# main.net
KiCad netlist of a schematic drawn in EAGLE
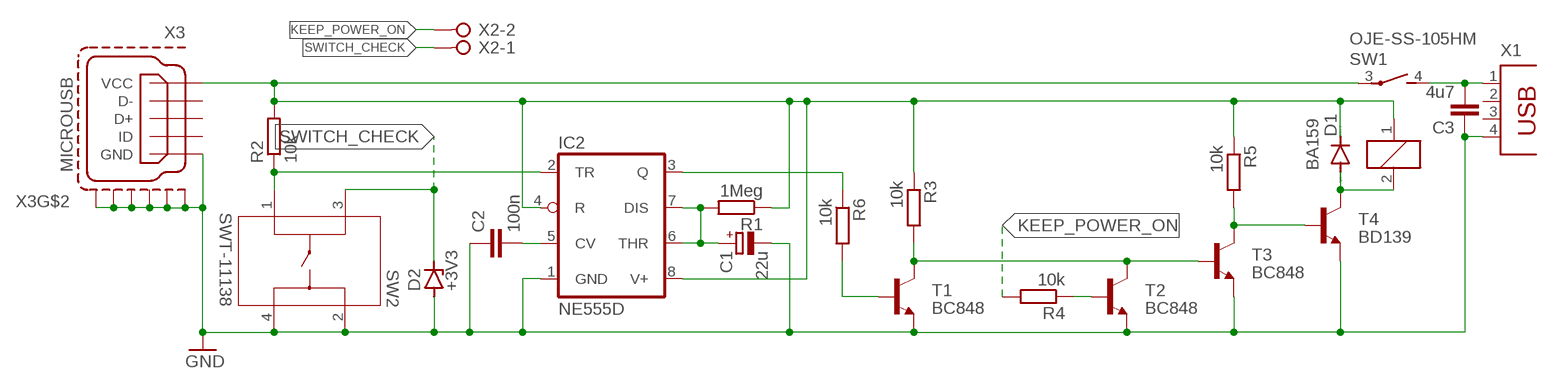
[diagram p0: schematic, sheet 1]

(export (version "E")
  (design (tool "Eeschema 10.0.6"))
  (components
    (comp (ref "C1")
      (value "22u")
      (footprint "eagle-import:SMC_B")
      (libsource (lib "eagle-import") (part "CPOL-EUSMCB"))
    )
    (comp (ref "C2")
      (value "100n")
      (footprint "eagle-import:C0805")
      (libsource (lib "eagle-import") (part "C-EUC0805"))
    )
    (comp (ref "C3")
      (value "4u7")
      (footprint "eagle-import:C050-075X075")
      (libsource (lib "eagle-import") (part "C-EU050-075X075"))
    )
    (comp (ref "D1")
      (value "BA159")
      (footprint "eagle-import:DO41-10")
      (libsource (lib "eagle-import") (part "1N4004"))
    )
    (comp (ref "D2")
      (value "+3V3")
      (footprint "eagle-import:SOD80C")
      (libsource (lib "eagle-import") (part "ZENER-DIODESOD80C"))
    )
    (comp (ref "IC2")
      (value "NE555D")
      (footprint "eagle-import:SO08")
      (libsource (lib "eagle-import") (part "555DNE"))
    )
    (comp (ref "R1")
      (value "1Meg")
      (footprint "eagle-import:R1206")
      (libsource (lib "eagle-import") (part "R-EU_R1206"))
    )
    (comp (ref "R2")
      (value "10k")
      (footprint "eagle-import:R1206")
      (libsource (lib "eagle-import") (part "R-EU_R1206"))
    )
    (comp (ref "R3")
      (value "10k")
      (footprint "eagle-import:R1206")
      (libsource (lib "eagle-import") (part "R-EU_R1206"))
    )
    (comp (ref "R4")
      (value "10k")
      (footprint "eagle-import:R1206")
      (libsource (lib "eagle-import") (part "R-EU_R1206"))
    )
    (comp (ref "R5")
      (value "10k")
      (footprint "eagle-import:R1206")
      (libsource (lib "eagle-import") (part "R-EU_R1206"))
    )
    (comp (ref "R6")
      (value "10k")
      (footprint "eagle-import:R1206")
      (libsource (lib "eagle-import") (part "R-EU_R1206"))
    )
    (comp (ref "SW1")
      (value "OJE-SS-105HM")
      (footprint "eagle-import:OJE-SS-105HM")
      (libsource (lib "eagle-import") (part "OJE-SS-105HM"))
    )
    (comp (ref "SW2")
      (value "SWT-11138")
      (footprint "eagle-import:SWT-11138")
      (libsource (lib "eagle-import") (part "SWT-11138"))
    )
    (comp (ref "T1")
      (value "BC848")
      (footprint "eagle-import:SOT23")
      (libsource (lib "eagle-import") (part "BC848"))
    )
    (comp (ref "T2")
      (value "BC848")
      (footprint "eagle-import:SOT23")
      (libsource (lib "eagle-import") (part "BC848"))
    )
    (comp (ref "T3")
      (value "BC848")
      (footprint "eagle-import:SOT23")
      (libsource (lib "eagle-import") (part "BC848"))
    )
    (comp (ref "T4")
      (value "BD139")
      (footprint "eagle-import:TO126")
      (libsource (lib "eagle-import") (part "BD139"))
    )
    (comp (ref "X1")
      (value "PN87520")
      (footprint "eagle-import:PN87520")
      (libsource (lib "eagle-import") (part "PN87520"))
    )
    (comp (ref "X2")
      (value "W237-02P")
      (footprint "eagle-import:W237-132")
      (libsource (lib "eagle-import") (part "W237-02P"))
    )
    (comp (ref "X3")
      (value "MICROUSB")
      (footprint "eagle-import:MICROUSB")
      (libsource (lib "eagle-import") (part "MICROUSB"))
    )
  )
  (nets
    (net (code "1") (name "GND") (class "Default")
      (node (ref "C1") (pin "-") (pinfunction "-_-") (pintype "passive"))
      (node (ref "C2") (pin "1") (pinfunction "1_1") (pintype "passive"))
      (node (ref "C3") (pin "1") (pinfunction "1_1") (pintype "passive"))
      (node (ref "D2") (pin "A") (pinfunction "A_A") (pintype "passive"))
      (node (ref "IC2") (pin "1") (pinfunction "GND_1") (pintype "power_in"))
      (node (ref "SW2") (pin "2") (pinfunction "4_2") (pintype "passive"))
      (node (ref "SW2") (pin "4") (pinfunction "3_4") (pintype "passive"))
      (node (ref "T1") (pin "2") (pinfunction "E_2") (pintype "passive"))
      (node (ref "T2") (pin "2") (pinfunction "E_2") (pintype "passive"))
      (node (ref "T3") (pin "2") (pinfunction "E_2") (pintype "passive"))
      (node (ref "T4") (pin "1") (pinfunction "E_1") (pintype "passive"))
      (node (ref "X1") (pin "4") (pinfunction "4_4") (pintype "passive"))
      (node (ref "X3") (pin "5") (pinfunction "GND_5") (pintype "input"))
      (node (ref "X3") (pin "P$1") (pinfunction "S1_P$1") (pintype "passive"))
      (node (ref "X3") (pin "P$2") (pinfunction "S2_P$2") (pintype "passive"))
      (node (ref "X3") (pin "P$3") (pinfunction "S3_P$3") (pintype "passive"))
      (node (ref "X3") (pin "P$4") (pinfunction "S4_P$4") (pintype "passive"))
      (node (ref "X3") (pin "P$5") (pinfunction "S5_P$5") (pintype "passive"))
      (node (ref "X3") (pin "P$6") (pinfunction "S6_P$6") (pintype "passive"))
    )
    (net (code "2") (name "KEEP_POWER_ON") (class "Default")
      (node (ref "R4") (pin "2") (pinfunction "2_2") (pintype "passive"))
      (node (ref "X2") (pin "2") (pinfunction "KL_2") (pintype "passive"))
    )
    (net (code "3") (name "Net-(IC2-CV)") (class "Default")
      (node (ref "C2") (pin "2") (pinfunction "2_2") (pintype "passive"))
      (node (ref "IC2") (pin "5") (pinfunction "CV_5") (pintype "input"))
    )
    (net (code "4") (name "Net-(IC2-DIS)") (class "Default")
      (node (ref "C1") (pin "+") (pinfunction "+_+") (pintype "passive"))
      (node (ref "IC2") (pin "6") (pinfunction "THR_6") (pintype "input"))
      (node (ref "IC2") (pin "7") (pinfunction "DIS_7") (pintype "input"))
      (node (ref "R1") (pin "2") (pinfunction "2_2") (pintype "passive"))
    )
    (net (code "5") (name "Net-(IC2-Q)") (class "Default")
      (node (ref "IC2") (pin "3") (pinfunction "Q_3") (pintype "output"))
      (node (ref "R6") (pin "1") (pinfunction "1_1") (pintype "passive"))
    )
    (net (code "6") (name "Net-(IC2-R)") (class "Default")
      (node (ref "D1") (pin "C") (pinfunction "C_C") (pintype "passive"))
      (node (ref "IC2") (pin "4") (pinfunction "R_4") (pintype "input"))
      (node (ref "IC2") (pin "8") (pinfunction "V+_8") (pintype "power_in"))
      (node (ref "R1") (pin "1") (pinfunction "1_1") (pintype "passive"))
      (node (ref "R2") (pin "2") (pinfunction "2_2") (pintype "passive"))
      (node (ref "R3") (pin "1") (pinfunction "1_1") (pintype "passive"))
      (node (ref "R5") (pin "1") (pinfunction "1_1") (pintype "passive"))
      (node (ref "SW1") (pin "1") (pinfunction "1_1") (pintype "passive"))
      (node (ref "SW1") (pin "3") (pinfunction "P_3") (pintype "passive"))
      (node (ref "X3") (pin "1") (pinfunction "VCC_1") (pintype "input"))
    )
    (net (code "7") (name "Net-(IC2-TR)") (class "Default")
      (node (ref "IC2") (pin "2") (pinfunction "TR_2") (pintype "input"))
      (node (ref "R2") (pin "1") (pinfunction "1_1") (pintype "passive"))
      (node (ref "SW2") (pin "1") (pinfunction "1_1") (pintype "passive"))
    )
    (net (code "8") (name "Net-(SW1B-S)") (class "Default")
      (node (ref "C3") (pin "2") (pinfunction "2_2") (pintype "passive"))
      (node (ref "SW1") (pin "4") (pinfunction "S_4") (pintype "passive"))
      (node (ref "X1") (pin "1") (pinfunction "1_1") (pintype "passive"))
    )
    (net (code "9") (name "Net-(T1-B)") (class "Default")
      (node (ref "R6") (pin "2") (pinfunction "2_2") (pintype "passive"))
      (node (ref "T1") (pin "1") (pinfunction "B_1") (pintype "passive"))
    )
    (net (code "10") (name "Net-(T1-C)") (class "Default")
      (node (ref "R3") (pin "2") (pinfunction "2_2") (pintype "passive"))
      (node (ref "T1") (pin "3") (pinfunction "C_3") (pintype "passive"))
      (node (ref "T2") (pin "3") (pinfunction "C_3") (pintype "passive"))
      (node (ref "T3") (pin "1") (pinfunction "B_1") (pintype "passive"))
    )
    (net (code "11") (name "Net-(T2-B)") (class "Default")
      (node (ref "R4") (pin "1") (pinfunction "1_1") (pintype "passive"))
      (node (ref "T2") (pin "1") (pinfunction "B_1") (pintype "passive"))
    )
    (net (code "12") (name "Net-(T3-C)") (class "Default")
      (node (ref "R5") (pin "2") (pinfunction "2_2") (pintype "passive"))
      (node (ref "T3") (pin "3") (pinfunction "C_3") (pintype "passive"))
      (node (ref "T4") (pin "3") (pinfunction "B_3") (pintype "passive"))
    )
    (net (code "13") (name "Net-(T4-C)") (class "Default")
      (node (ref "D1") (pin "A") (pinfunction "A_A") (pintype "passive"))
      (node (ref "SW1") (pin "2") (pinfunction "2_2") (pintype "passive"))
      (node (ref "T4") (pin "2") (pinfunction "C_2") (pintype "passive"))
    )
    (net (code "14") (name "SWITCH_CHECK") (class "Default")
      (node (ref "D2") (pin "C") (pinfunction "C_C") (pintype "passive"))
      (node (ref "SW2") (pin "3") (pinfunction "2_3") (pintype "passive"))
      (node (ref "X2") (pin "1") (pinfunction "KL_1") (pintype "passive"))
    )
    (net (code "15") (name "unconnected-(X1-Pad2)") (class "Default")
      (node (ref "X1") (pin "2") (pinfunction "2_2") (pintype "passive"))
    )
    (net (code "16") (name "unconnected-(X1-Pad3)") (class "Default")
      (node (ref "X1") (pin "3") (pinfunction "3_3") (pintype "passive"))
    )
    (net (code "17") (name "unconnected-(X3A-D+-Pad3)") (class "Default")
      (node (ref "X3") (pin "3") (pinfunction "D+_3") (pintype "input"))
    )
    (net (code "18") (name "unconnected-(X3A-D--Pad2)") (class "Default")
      (node (ref "X3") (pin "2") (pinfunction "D-_2") (pintype "input"))
    )
    (net (code "19") (name "unconnected-(X3A-ID-Pad4)") (class "Default")
      (node (ref "X3") (pin "4") (pinfunction "ID_4") (pintype "input"))
    )
  )
)
